# Short_to_GND_protection.net
KiCad netlist of a schematic drawn in Altium Designer
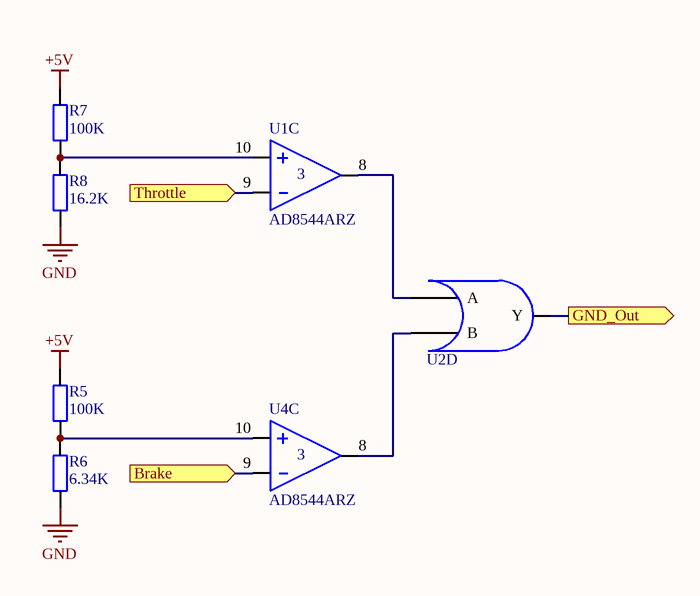
[diagram p0: Short to GND protection.SchDoc]

(export (version "E")
  (design (tool "Eeschema 10.0.6"))
  (components
    (comp (ref "R5")
      (value "100K")
      (footprint "RESC160X80X50L30N")
      (fields
        (field (name "PART NUMBER") "R_0603_100K_0W1_C")
        (field (name "MANUFACTURER PART NUMBER") "CRCW0603100KFKEAC")
      )
      (libsource (lib "FR") (part "Resistor"))
    )
    (comp (ref "R6")
      (value "6.34K")
      (footprint "RESC160X80X55L25N")
      (fields
        (field (name "PART NUMBER") "R_0603_6.34K_0W1")
        (field (name "MANUFACTURER PART NUMBER") "AC0603FR-076K34L")
      )
      (libsource (lib "FR") (part "Resistor"))
    )
    (comp (ref "R7")
      (value "100K")
      (footprint "RESC160X80X50L30N")
      (fields
        (field (name "PART NUMBER") "R_0603_100K_0W1_C")
        (field (name "MANUFACTURER PART NUMBER") "CRCW0603100KFKEAC")
      )
      (libsource (lib "FR") (part "Resistor"))
    )
    (comp (ref "R8")
      (value "16.2K")
      (footprint "RESC157X85X50L30N")
      (fields
        (field (name "PART NUMBER") "R_0603_16.2K_0W1")
        (field (name "MANUFACTURER PART NUMBER") "CRCW060316K2FKEA")
      )
      (libsource (lib "FR") (part "Resistor"))
    )
    (comp (ref "U1")
      (value "AD8544ARZ")
      (footprint "SOIC14P127_865X600X175L83X41N")
      (fields
        (field (name "PART NUMBER") "AD8544")
        (field (name "MANUFACTURER PART NUMBER") "AD8544ARZ-REEL")
      )
      (libsource (lib "FR") (part "AD8544"))
    )
    (comp (ref "U2")
      (value "CD4071BM")
      (footprint "SOIC14P127_865X600X175L70X42N")
      (libsource (lib "FR") (part "HEF4071B"))
    )
    (comp (ref "U4")
      (value "AD8544ARZ")
      (footprint "SOIC14P127_865X600X175L83X41N")
      (fields
        (field (name "PART NUMBER") "AD8544")
        (field (name "MANUFACTURER PART NUMBER") "AD8544ARZ-REEL")
      )
      (libsource (lib "FR") (part "AD8544"))
    )
  )
  (nets
    (net (code "1") (name "+5V") (class "Default")
      (node (ref "R5") (pin "2") (pinfunction "2_2") (pintype "passive"))
      (node (ref "R7") (pin "2") (pinfunction "2_2") (pintype "passive"))
    )
    (net (code "2") (name "/Brake") (class "Default") (node (ref "U4") (pin "9") (pintype "passive")))
    (net (code "3") (name "/GND_Out") (class "Default")
      (node (ref "U2") (pin "11") (pinfunction "Y_11") (pintype "passive"))
    )
    (net (code "4") (name "/Throttle") (class "Default") (node (ref "U1") (pin "9") (pintype "passive")))
    (net (code "5") (name "GND") (class "Default")
      (node (ref "R6") (pin "2") (pinfunction "2_2") (pintype "passive"))
      (node (ref "R8") (pin "1") (pinfunction "1_1") (pintype "passive"))
    )
    (net (code "6") (name "Net-(R5-Pad1)") (class "Default")
      (node (ref "R5") (pin "1") (pinfunction "1_1") (pintype "passive"))
      (node (ref "R6") (pin "1") (pinfunction "1_1") (pintype "passive"))
      (node (ref "U4") (pin "10") (pintype "passive"))
    )
    (net (code "7") (name "Net-(R7-Pad1)") (class "Default")
      (node (ref "R7") (pin "1") (pinfunction "1_1") (pintype "passive"))
      (node (ref "R8") (pin "2") (pinfunction "2_2") (pintype "passive"))
      (node (ref "U1") (pin "10") (pintype "passive"))
    )
    (net (code "8") (name "Net-(U2D-A)") (class "Default")
      (node (ref "U1") (pin "8") (pintype "passive"))
      (node (ref "U2") (pin "12") (pinfunction "A_12") (pintype "passive"))
    )
    (net (code "9") (name "Net-(U2D-B)") (class "Default")
      (node (ref "U2") (pin "13") (pinfunction "B_13") (pintype "passive"))
      (node (ref "U4") (pin "8") (pintype "passive"))
    )
  )
)
